# schematic.net
KiCad netlist of a schematic drawn in EAGLE
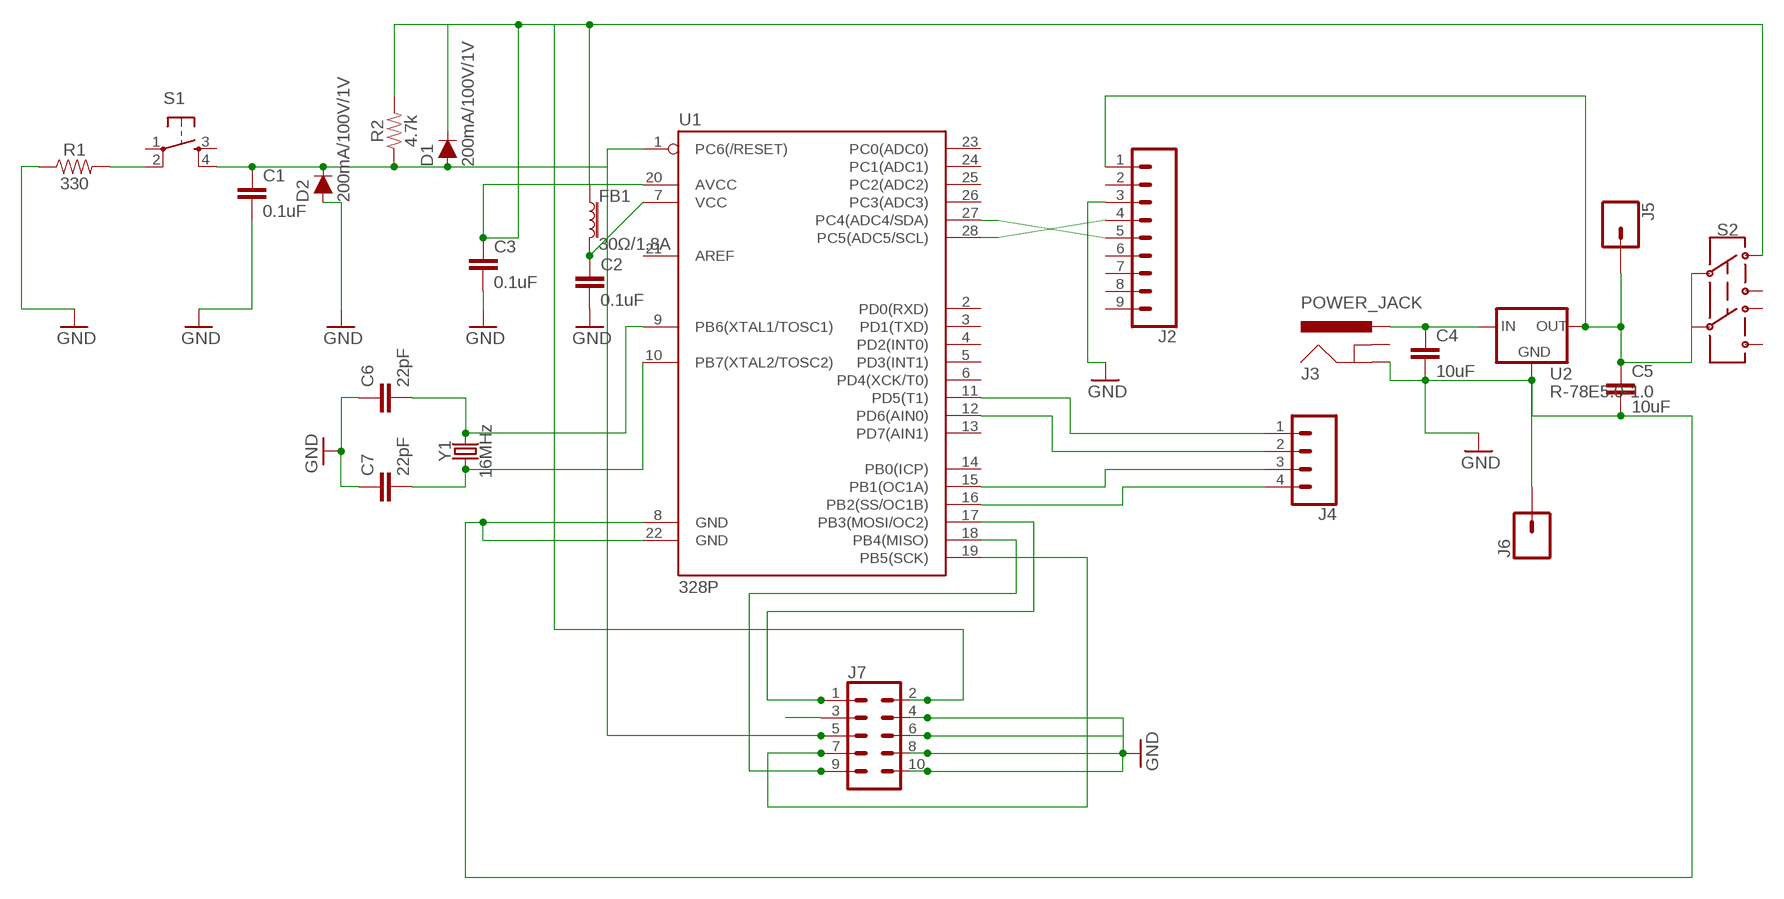
[diagram p0: schematic, sheet 1]

(export (version "E")
  (design (tool "Eeschema 10.0.6"))
  (components
    (comp (ref "C1")
      (value "0.1uF")
      (footprint "eagle-import:0603")
      (libsource (lib "eagle-import") (part "0.1UF-0603-25V-(+80/-20%)"))
    )
    (comp (ref "C2")
      (value "0.1uF")
      (footprint "eagle-import:0603")
      (libsource (lib "eagle-import") (part "0.1UF-0603-25V-(+80/-20%)"))
    )
    (comp (ref "C3")
      (value "0.1uF")
      (footprint "eagle-import:0603")
      (libsource (lib "eagle-import") (part "0.1UF-0603-25V-(+80/-20%)"))
    )
    (comp (ref "C4")
      (value "10uF")
      (footprint "eagle-import:0603")
      (libsource (lib "eagle-import") (part "10UF-0603-6.3V-20%"))
    )
    (comp (ref "C5")
      (value "10uF")
      (footprint "eagle-import:0603")
      (libsource (lib "eagle-import") (part "10UF-0603-6.3V-20%"))
    )
    (comp (ref "C6")
      (value "22pF")
      (footprint "eagle-import:0603")
      (libsource (lib "eagle-import") (part "22PF-0603-50V-5%"))
    )
    (comp (ref "C7")
      (value "22pF")
      (footprint "eagle-import:0603")
      (libsource (lib "eagle-import") (part "22PF-0603-50V-5%"))
    )
    (comp (ref "D1")
      (value "200mA/100V/1V")
      (footprint "eagle-import:DIODE-1N4148")
      (libsource (lib "eagle-import") (part "DIODE-1N4148"))
    )
    (comp (ref "D2")
      (value "200mA/100V/1V")
      (footprint "eagle-import:DIODE-1N4148")
      (libsource (lib "eagle-import") (part "DIODE-1N4148"))
    )
    (comp (ref "FB1")
      (value "30Ω/1.8A")
      (footprint "eagle-import:0603")
      (libsource (lib "eagle-import") (part "FERRITE_BEAD-0603"))
    )
    (comp (ref "J2")
      (value "CONN_09")
      (footprint "eagle-import:1X09")
      (libsource (lib "eagle-import") (part "CONN_09"))
    )
    (comp (ref "J3")
      (value "POWER_JACK")
      (footprint "eagle-import:POWER_JACK_PTH")
      (libsource (lib "eagle-import") (part "POWER_JACK"))
    )
    (comp (ref "J4")
      (value "CONN_04")
      (footprint "eagle-import:1X04")
      (libsource (lib "eagle-import") (part "CONN_04"))
    )
    (comp (ref "J5")
      (value "CONN_01")
      (footprint "eagle-import:1X01")
      (libsource (lib "eagle-import") (part "CONN_01"))
    )
    (comp (ref "J6")
      (value "CONN_01")
      (footprint "eagle-import:1X01")
      (libsource (lib "eagle-import") (part "CONN_01"))
    )
    (comp (ref "J7")
      (value "CONN_05X2SHD")
      (footprint "eagle-import:2X5-SHROUDED")
      (libsource (lib "eagle-import") (part "CONN_05X2SHD"))
    )
    (comp (ref "R1")
      (value "330")
      (footprint "eagle-import:0603")
      (libsource (lib "eagle-import") (part "330OHM-0603-1/10W-1%"))
    )
    (comp (ref "R2")
      (value "4.7k")
      (footprint "eagle-import:0603")
      (libsource (lib "eagle-import") (part "4.7KOHM-0603-1/10W-1%"))
    )
    (comp (ref "S1")
      (value "TAC_SWITCHPTH")
      (footprint "eagle-import:TACTILE-PTH")
      (libsource (lib "eagle-import") (part "TAC_SWITCHPTH"))
    )
    (comp (ref "S2")
      (value "SWITCH-DPDT-SMD-AYZ0202")
      (footprint "eagle-import:SWITCH_DPDT_SMD_AYZ0202")
      (libsource (lib "eagle-import") (part "SWITCH-DPDT-SMD-AYZ0202"))
    )
    (comp (ref "U1")
      (value "328P")
      (footprint "eagle-import:DIP28")
      (libsource (lib "eagle-import") (part "ATMEGA328P_PDIP"))
    )
    (comp (ref "U2")
      (value "R-78E5.0-1.0")
      (footprint "eagle-import:DC-DC_CONVERTER_78XX")
      (libsource (lib "eagle-import") (part "R-78E5.0-1.0"))
    )
    (comp (ref "Y1")
      (value "16MHz")
      (footprint "eagle-import:HC49US")
      (libsource (lib "eagle-import") (part "CRYSTAL-16MHZPTH-HC49US"))
    )
  )
  (nets
    (net (code "1") (name "GND") (class "Default")
      (node (ref "C1") (pin "2") (pinfunction "2_2") (pintype "passive"))
      (node (ref "C2") (pin "2") (pinfunction "2_2") (pintype "passive"))
      (node (ref "C3") (pin "2") (pinfunction "2_2") (pintype "passive"))
      (node (ref "C4") (pin "2") (pinfunction "2_2") (pintype "passive"))
      (node (ref "C5") (pin "2") (pinfunction "2_2") (pintype "passive"))
      (node (ref "C6") (pin "1") (pinfunction "1_1") (pintype "passive"))
      (node (ref "C7") (pin "1") (pinfunction "1_1") (pintype "passive"))
      (node (ref "D2") (pin "A") (pinfunction "A_A") (pintype "passive"))
      (node (ref "J2") (pin "3") (pinfunction "3_3") (pintype "passive"))
      (node (ref "J3") (pin "GND") (pinfunction "GND_GND") (pintype "bidirectional"))
      (node (ref "J6") (pin "1") (pinfunction "1_1") (pintype "passive"))
      (node (ref "J7") (pin "10") (pinfunction "10_10") (pintype "passive"))
      (node (ref "J7") (pin "4") (pinfunction "4_4") (pintype "passive"))
      (node (ref "J7") (pin "6") (pinfunction "6_6") (pintype "passive"))
      (node (ref "J7") (pin "8") (pinfunction "8_8") (pintype "passive"))
      (node (ref "R1") (pin "1") (pinfunction "1_1") (pintype "passive"))
      (node (ref "U1") (pin "22") (pinfunction "GND_22") (pintype "bidirectional"))
      (node (ref "U1") (pin "8") (pinfunction "GND_8") (pintype "bidirectional"))
      (node (ref "U2") (pin "GND") (pinfunction "GND_GND") (pintype "input"))
    )
    (net (code "2") (name "Net-(R1-Pad2)") (class "Default")
      (node (ref "R1") (pin "2") (pinfunction "2_2") (pintype "passive"))
      (node (ref "S1") (pin "2") (pinfunction "2_2") (pintype "passive"))
    )
    (net (code "3") (name "Net-(U1-AVCC)") (class "Default")
      (node (ref "C3") (pin "1") (pinfunction "1_1") (pintype "passive"))
      (node (ref "D1") (pin "C") (pinfunction "C_C") (pintype "passive"))
      (node (ref "FB1") (pin "1") (pinfunction "1_1") (pintype "passive"))
      (node (ref "J7") (pin "2") (pinfunction "2_2") (pintype "passive"))
      (node (ref "R2") (pin "2") (pinfunction "2_2") (pintype "passive"))
      (node (ref "S2") (pin "1") (pinfunction "1_1") (pintype "bidirectional"))
      (node (ref "U1") (pin "20") (pinfunction "AVCC_20") (pintype "bidirectional"))
    )
    (net (code "4") (name "Net-(U1-PB1(OC1A))") (class "Default")
      (node (ref "J4") (pin "3") (pinfunction "3_3") (pintype "passive"))
      (node (ref "U1") (pin "15") (pinfunction "PB1(OC1A)_15") (pintype "bidirectional"))
    )
    (net (code "5") (name "Net-(U1-PB2(SS{slash}OC1B))") (class "Default")
      (node (ref "J4") (pin "4") (pinfunction "4_4") (pintype "passive"))
      (node (ref "U1") (pin "16") (pinfunction "PB2(SS/OC1B)_16") (pintype "bidirectional"))
    )
    (net (code "6") (name "Net-(U1-PB3(MOSI{slash}OC2))") (class "Default")
      (node (ref "J7") (pin "1") (pinfunction "1_1") (pintype "passive"))
      (node (ref "U1") (pin "17") (pinfunction "PB3(MOSI/OC2)_17") (pintype "bidirectional"))
    )
    (net (code "7") (name "Net-(U1-PB4(MISO))") (class "Default")
      (node (ref "J7") (pin "9") (pinfunction "9_9") (pintype "passive"))
      (node (ref "U1") (pin "18") (pinfunction "PB4(MISO)_18") (pintype "bidirectional"))
    )
    (net (code "8") (name "Net-(U1-PB5(SCK))") (class "Default")
      (node (ref "J7") (pin "7") (pinfunction "7_7") (pintype "passive"))
      (node (ref "U1") (pin "19") (pinfunction "PB5(SCK)_19") (pintype "bidirectional"))
    )
    (net (code "9") (name "Net-(U1-PB6(XTAL1{slash}TOSC1))") (class "Default")
      (node (ref "C6") (pin "2") (pinfunction "2_2") (pintype "passive"))
      (node (ref "U1") (pin "9") (pinfunction "PB6(XTAL1/TOSC1)_9") (pintype "bidirectional"))
      (node (ref "Y1") (pin "2") (pinfunction "2_2") (pintype "passive"))
    )
    (net (code "10") (name "Net-(U1-PB7(XTAL2{slash}TOSC2))") (class "Default")
      (node (ref "C7") (pin "2") (pinfunction "2_2") (pintype "passive"))
      (node (ref "U1") (pin "10") (pinfunction "PB7(XTAL2/TOSC2)_10") (pintype "bidirectional"))
      (node (ref "Y1") (pin "1") (pinfunction "1_1") (pintype "passive"))
    )
    (net (code "11") (name "Net-(U1-PC4(ADC4{slash}SDA))") (class "Default")
      (node (ref "J2") (pin "5") (pinfunction "5_5") (pintype "passive"))
      (node (ref "U1") (pin "27") (pinfunction "PC4(ADC4/SDA)_27") (pintype "bidirectional"))
    )
    (net (code "12") (name "Net-(U1-PC5(ADC5{slash}SCL))") (class "Default")
      (node (ref "J2") (pin "4") (pinfunction "4_4") (pintype "passive"))
      (node (ref "U1") (pin "28") (pinfunction "PC5(ADC5/SCL)_28") (pintype "bidirectional"))
    )
    (net (code "13") (name "Net-(U1-PC6({slash}RESET))") (class "Default")
      (node (ref "C1") (pin "1") (pinfunction "1_1") (pintype "passive"))
      (node (ref "D1") (pin "A") (pinfunction "A_A") (pintype "passive"))
      (node (ref "D2") (pin "C") (pinfunction "C_C") (pintype "passive"))
      (node (ref "J7") (pin "5") (pinfunction "5_5") (pintype "passive"))
      (node (ref "R2") (pin "1") (pinfunction "1_1") (pintype "passive"))
      (node (ref "S1") (pin "4") (pinfunction "4_4") (pintype "passive"))
      (node (ref "U1") (pin "1") (pinfunction "PC6(/RESET)_1") (pintype "bidirectional"))
    )
    (net (code "14") (name "Net-(U1-PD5(T1))") (class "Default")
      (node (ref "J4") (pin "1") (pinfunction "1_1") (pintype "passive"))
      (node (ref "U1") (pin "11") (pinfunction "PD5(T1)_11") (pintype "bidirectional"))
    )
    (net (code "15") (name "Net-(U1-PD6(AIN0))") (class "Default")
      (node (ref "J4") (pin "2") (pinfunction "2_2") (pintype "passive"))
      (node (ref "U1") (pin "12") (pinfunction "PD6(AIN0)_12") (pintype "bidirectional"))
    )
    (net (code "16") (name "Net-(U1-VCC)") (class "Default")
      (node (ref "C2") (pin "1") (pinfunction "1_1") (pintype "passive"))
      (node (ref "FB1") (pin "2") (pinfunction "2_2") (pintype "passive"))
      (node (ref "U1") (pin "7") (pinfunction "VCC_7") (pintype "bidirectional"))
    )
    (net (code "17") (name "Net-(U2-IN)") (class "Default")
      (node (ref "C4") (pin "1") (pinfunction "1_1") (pintype "passive"))
      (node (ref "J3") (pin "PWR") (pinfunction "PWR_PWR") (pintype "bidirectional"))
      (node (ref "U2") (pin "VIN") (pinfunction "IN_VIN") (pintype "input"))
    )
    (net (code "18") (name "Net-(U2-OUT)") (class "Default")
      (node (ref "C5") (pin "1") (pinfunction "1_1") (pintype "passive"))
      (node (ref "J2") (pin "1") (pinfunction "1_1") (pintype "passive"))
      (node (ref "J5") (pin "1") (pinfunction "1_1") (pintype "passive"))
      (node (ref "S2") (pin "2") (pinfunction "2_2") (pintype "bidirectional"))
      (node (ref "U2") (pin "VOUT") (pinfunction "OUT_VOUT") (pintype "passive"))
    )
    (net (code "19") (name "unconnected-(J2-Pad2)") (class "Default")
      (node (ref "J2") (pin "2") (pinfunction "2_2") (pintype "passive"))
    )
    (net (code "20") (name "unconnected-(J2-Pad6)") (class "Default")
      (node (ref "J2") (pin "6") (pinfunction "6_6") (pintype "passive"))
    )
    (net (code "21") (name "unconnected-(J2-Pad7)") (class "Default")
      (node (ref "J2") (pin "7") (pinfunction "7_7") (pintype "passive"))
    )
    (net (code "22") (name "unconnected-(J2-Pad8)") (class "Default")
      (node (ref "J2") (pin "8") (pinfunction "8_8") (pintype "passive"))
    )
    (net (code "23") (name "unconnected-(J2-Pad9)") (class "Default")
      (node (ref "J2") (pin "9") (pinfunction "9_9") (pintype "passive"))
    )
    (net (code "24") (name "unconnected-(J3-PadGNDBREAK)") (class "Default")
      (node (ref "J3") (pin "GNDBREAK") (pinfunction "GNDBREAK_GNDBREAK") (pintype "bidirectional"))
    )
    (net (code "25") (name "unconnected-(J7-Pad3)") (class "Default")
      (node (ref "J7") (pin "3") (pinfunction "3_3") (pintype "passive"))
    )
    (net (code "26") (name "unconnected-(S1-Pad1)") (class "Default")
      (node (ref "S1") (pin "1") (pinfunction "1_1") (pintype "passive"))
    )
    (net (code "27") (name "unconnected-(S1-Pad3)") (class "Default")
      (node (ref "S1") (pin "3") (pinfunction "3_3") (pintype "passive"))
    )
    (net (code "28") (name "unconnected-(S2-Pad3)") (class "Default")
      (node (ref "S2") (pin "3") (pinfunction "3_3") (pintype "bidirectional"))
    )
    (net (code "29") (name "unconnected-(S2-Pad4)") (class "Default")
      (node (ref "S2") (pin "4") (pinfunction "4_4") (pintype "bidirectional"))
    )
    (net (code "30") (name "unconnected-(S2-Pad5)") (class "Default")
      (node (ref "S2") (pin "5") (pinfunction "5_5") (pintype "bidirectional"))
    )
    (net (code "31") (name "unconnected-(S2-Pad6)") (class "Default")
      (node (ref "S2") (pin "6") (pinfunction "6_6") (pintype "bidirectional"))
    )
    (net (code "32") (name "unconnected-(U1-AREF-Pad21)") (class "Default")
      (node (ref "U1") (pin "21") (pinfunction "AREF_21") (pintype "bidirectional"))
    )
    (net (code "33") (name "unconnected-(U1-PB0(ICP)-Pad14)") (class "Default")
      (node (ref "U1") (pin "14") (pinfunction "PB0(ICP)_14") (pintype "bidirectional"))
    )
    (net (code "34") (name "unconnected-(U1-PC0(ADC0)-Pad23)") (class "Default")
      (node (ref "U1") (pin "23") (pinfunction "PC0(ADC0)_23") (pintype "bidirectional"))
    )
    (net (code "35") (name "unconnected-(U1-PC1(ADC1)-Pad24)") (class "Default")
      (node (ref "U1") (pin "24") (pinfunction "PC1(ADC1)_24") (pintype "bidirectional"))
    )
    (net (code "36") (name "unconnected-(U1-PC2(ADC2)-Pad25)") (class "Default")
      (node (ref "U1") (pin "25") (pinfunction "PC2(ADC2)_25") (pintype "bidirectional"))
    )
    (net (code "37") (name "unconnected-(U1-PC3(ADC3)-Pad26)") (class "Default")
      (node (ref "U1") (pin "26") (pinfunction "PC3(ADC3)_26") (pintype "bidirectional"))
    )
    (net (code "38") (name "unconnected-(U1-PD0(RXD)-Pad2)") (class "Default")
      (node (ref "U1") (pin "2") (pinfunction "PD0(RXD)_2") (pintype "bidirectional"))
    )
    (net (code "39") (name "unconnected-(U1-PD1(TXD)-Pad3)") (class "Default")
      (node (ref "U1") (pin "3") (pinfunction "PD1(TXD)_3") (pintype "bidirectional"))
    )
    (net (code "40") (name "unconnected-(U1-PD2(INT0)-Pad4)") (class "Default")
      (node (ref "U1") (pin "4") (pinfunction "PD2(INT0)_4") (pintype "bidirectional"))
    )
    (net (code "41") (name "unconnected-(U1-PD3(INT1)-Pad5)") (class "Default")
      (node (ref "U1") (pin "5") (pinfunction "PD3(INT1)_5") (pintype "bidirectional"))
    )
    (net (code "42") (name "unconnected-(U1-PD4(XCK{slash}T0)-Pad6)") (class "Default")
      (node (ref "U1") (pin "6") (pinfunction "PD4(XCK/T0)_6") (pintype "bidirectional"))
    )
    (net (code "43") (name "unconnected-(U1-PD7(AIN1)-Pad13)") (class "Default")
      (node (ref "U1") (pin "13") (pinfunction "PD7(AIN1)_13") (pintype "bidirectional"))
    )
  )
)
